# A-1_SINGLE_STEP_2021-06-04.net
KiCad netlist of a schematic drawn in EasyEDA
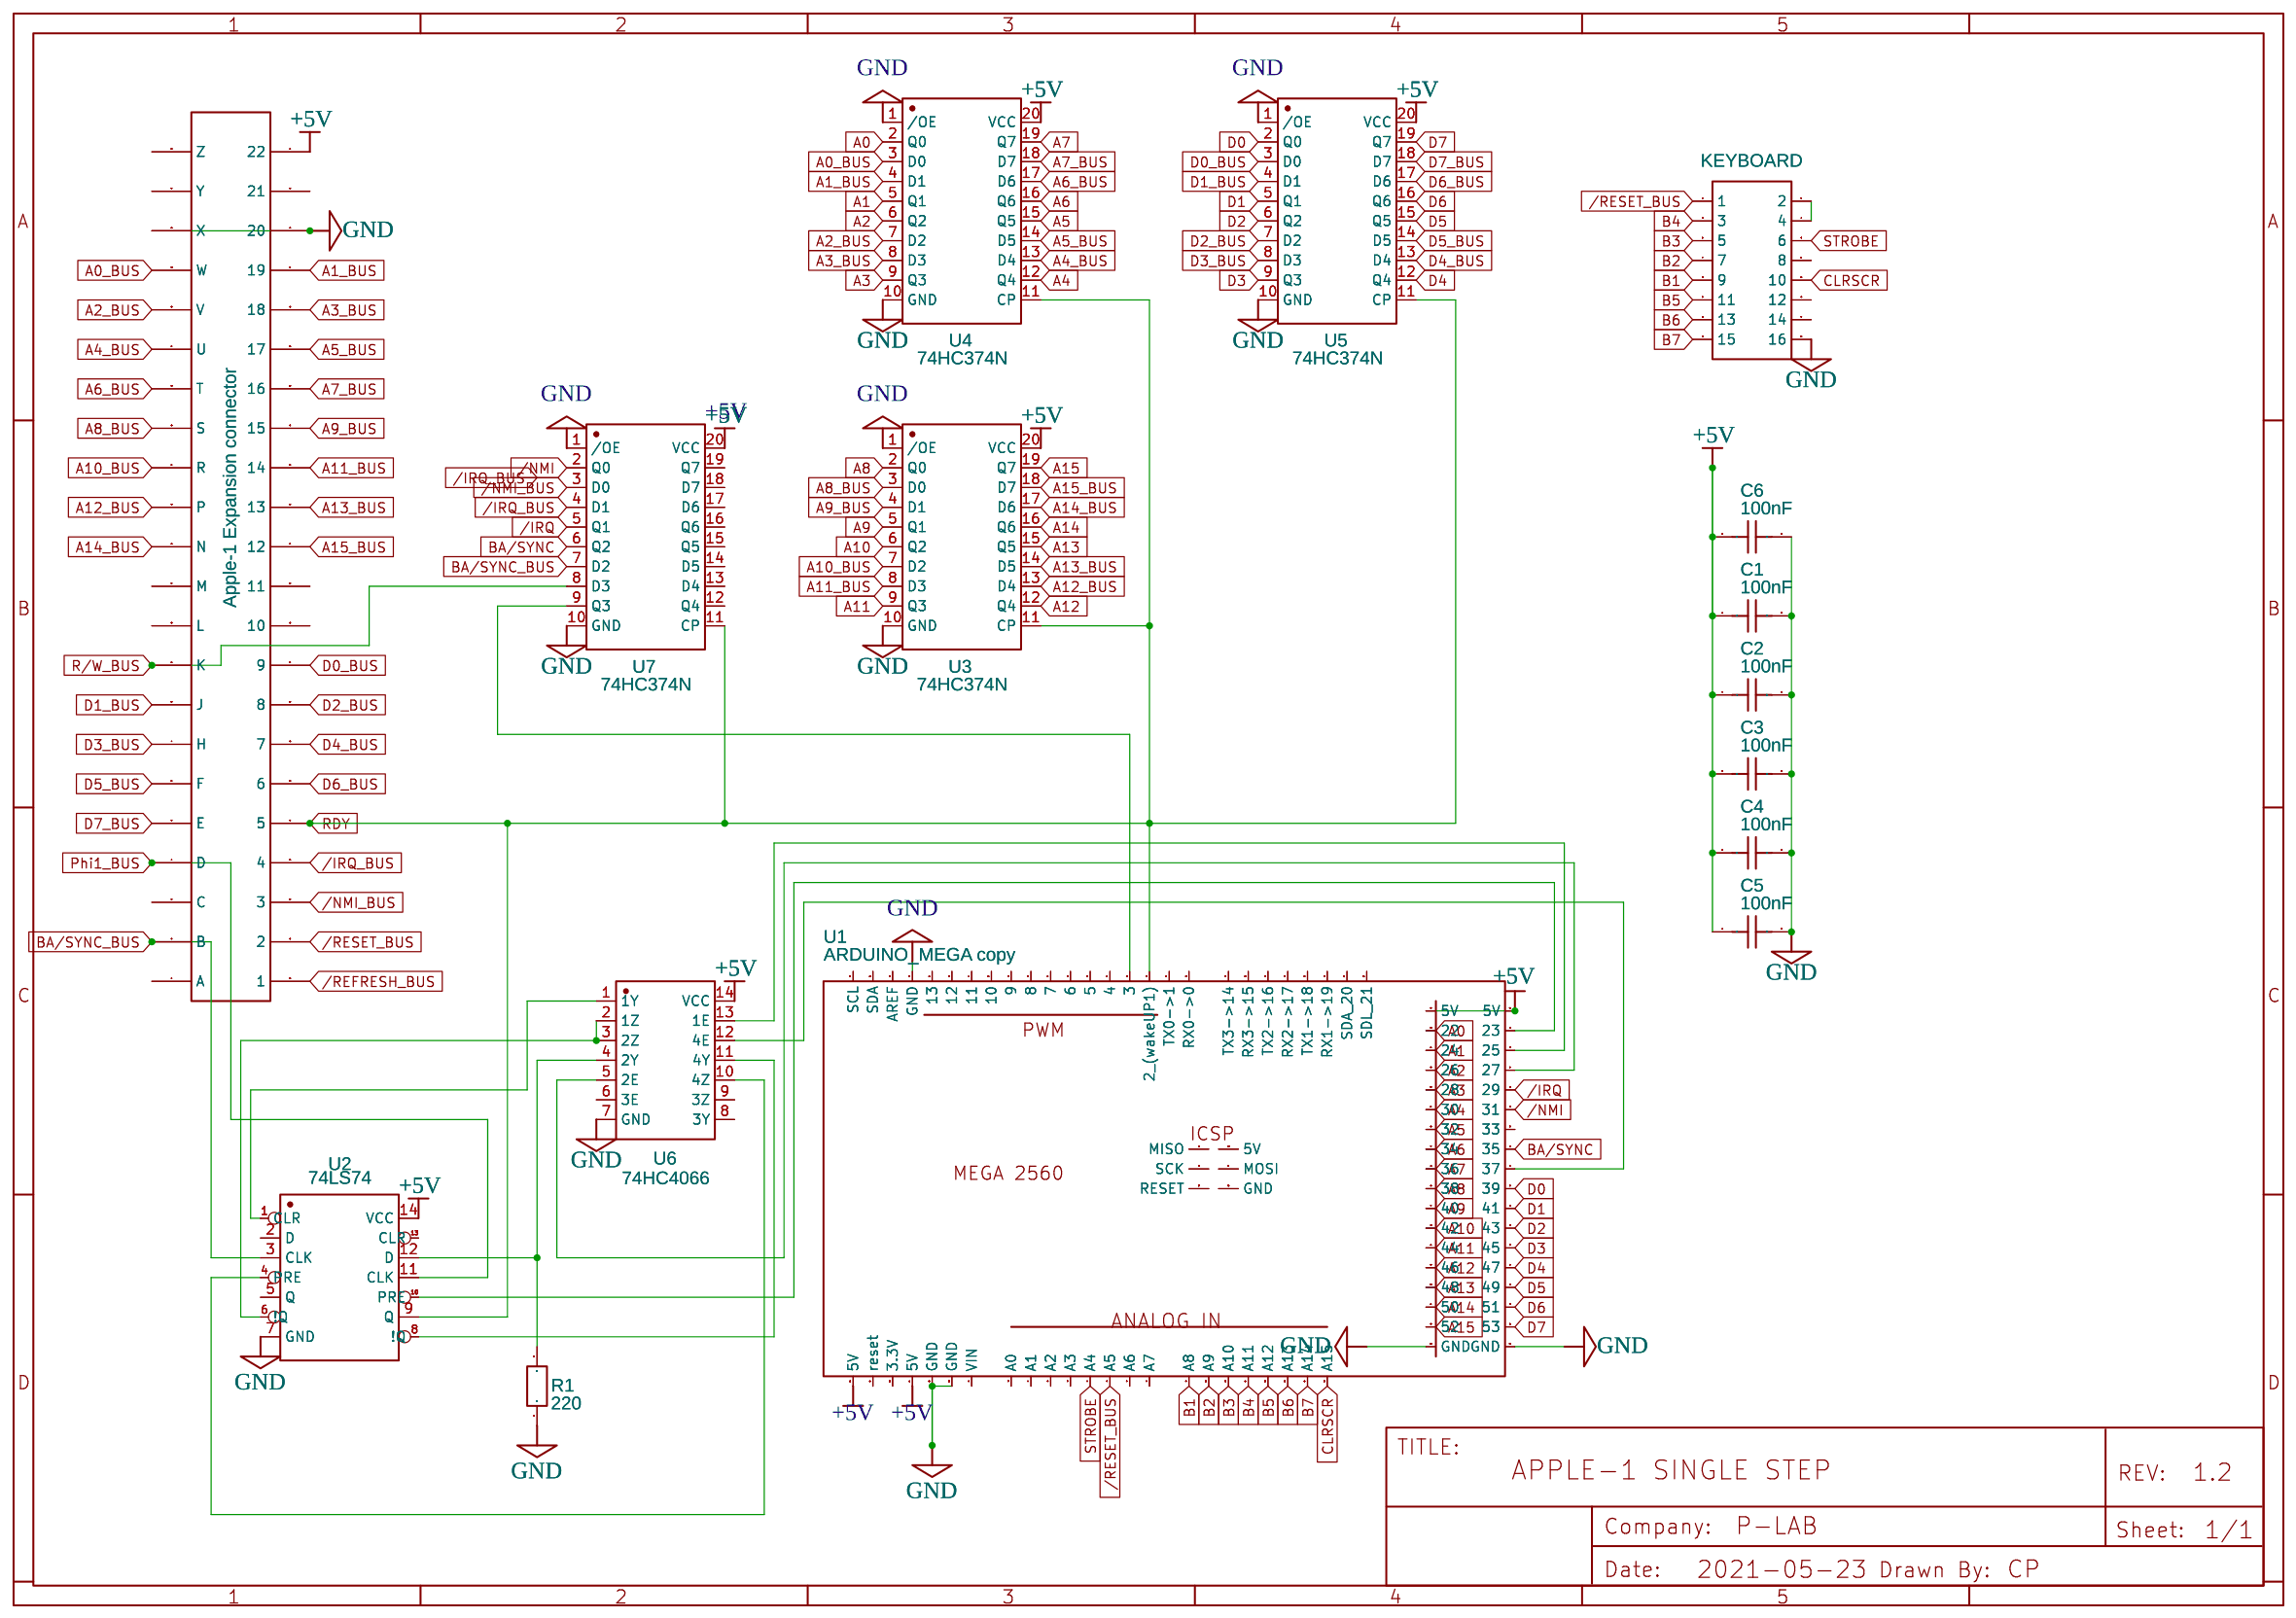
[diagram p0: schematic sheet]

(export (version "E")
  (design (tool "Eeschema 10.0.6"))
  (components
    (comp (ref "C1")
      (value "100nF")
      (fields
        (field (name "BOM_Manufacturer Part") "CT4G-0805-2X1-50V-0.1uF-K")
        (field (name "BOM_Supplier Part") "C141981")
      )
      (libsource (lib "") (part "CT4G-0805-2X1-50V-0.1UF-K"))
    )
    (comp (ref "C2")
      (value "100nF")
      (fields
        (field (name "BOM_Manufacturer Part") "CT4G-0805-2X1-50V-0.1uF-K")
        (field (name "BOM_Supplier Part") "C141981")
      )
      (libsource (lib "") (part "CT4G-0805-2X1-50V-0.1UF-K"))
    )
    (comp (ref "C3")
      (value "100nF")
      (fields
        (field (name "BOM_Manufacturer Part") "CT4G-0805-2X1-50V-0.1uF-K")
        (field (name "BOM_Supplier Part") "C141981")
      )
      (libsource (lib "") (part "CT4G-0805-2X1-50V-0.1UF-K"))
    )
    (comp (ref "C4")
      (value "100nF")
      (fields
        (field (name "BOM_Manufacturer Part") "CT4G-0805-2X1-50V-0.1uF-K")
        (field (name "BOM_Supplier Part") "C141981")
      )
      (libsource (lib "") (part "CT4G-0805-2X1-50V-0.1UF-K"))
    )
    (comp (ref "C5")
      (value "100nF")
      (fields
        (field (name "BOM_Manufacturer Part") "CT4G-0805-2X1-50V-0.1uF-K")
        (field (name "BOM_Supplier Part") "C141981")
      )
      (libsource (lib "") (part "CT4G-0805-2X1-50V-0.1UF-K"))
    )
    (comp (ref "C6")
      (value "100nF")
      (fields
        (field (name "BOM_Manufacturer Part") "CT4G-0805-2X1-50V-0.1uF-K")
        (field (name "BOM_Supplier Part") "C141981")
      )
      (libsource (lib "") (part "CT4G-0805-2X1-50V-0.1UF-K"))
    )
    (comp (ref "J1")
      (value "Apple-1 Expansion connector")
      (fields (field (name "BOM_Manufacturer Part") "306-018-520-102"))
      (libsource (lib "") (part "EDAC_Card_Edge_Female_2x22_pin_3.96mm"))
    )
    (comp (ref "KEYBOARD") (value "Header 2x8") (libsource (lib "") (part "Header 2x8")))
    (comp (ref "R1")
      (value "220")
      (fields
        (field (name "BOM_Manufacturer Part") "RN 1/4W 2R F T/B A1")
        (field (name "BOM_Supplier Part") "C410658")
      )
      (libsource (lib "") (part "RN 1/4W 2R F T/B A1"))
    )
    (comp (ref "U1")
      (value "ARDUINO_MEGA copy")
      (fields (field (name "BOM_Manufacturer Part") "ARDUINO MEGA"))
      (libsource (lib "") (part "ARDUINO_MEGA copy"))
    )
    (comp (ref "U2") (value "74LS74") (libsource (lib "") (part "7474")))
    (comp (ref "U3") (value "74HC374N") (libsource (lib "") (part "74HC374N")))
    (comp (ref "U4") (value "74HC374N") (libsource (lib "") (part "74HC374N")))
    (comp (ref "U5") (value "74HC374N") (libsource (lib "") (part "74HC374N")))
    (comp (ref "U6")
      (value "74HC4066")
      (fields
        (field (name "BOM_Manufacturer Part") "74HC4066D-Q100,118")
        (field (name "BOM_Supplier Part") "C547030")
      )
      (libsource (lib "") (part "74HC4066D-Q100,118"))
    )
    (comp (ref "U7") (value "74HC374N") (libsource (lib "") (part "74HC374N")))
  )
  (nets
    (net (code "1") (name "+5V") (class "Default")
      (node (ref "C1") (pin "1") (pinfunction "1_1") (pintype "unspecified"))
      (node (ref "C2") (pin "1") (pinfunction "1_1") (pintype "unspecified"))
      (node (ref "C3") (pin "1") (pinfunction "1_1") (pintype "unspecified"))
      (node (ref "C4") (pin "1") (pinfunction "1_1") (pintype "unspecified"))
      (node (ref "C5") (pin "1") (pinfunction "1_1") (pintype "unspecified"))
      (node (ref "C6") (pin "1") (pinfunction "1_1") (pintype "unspecified"))
      (node (ref "J1") (pin "44") (pinfunction "22_44") (pintype "unspecified"))
      (node (ref "U1") (pin "5V") (pinfunction "5V_5V") (pintype "unspecified"))
      (node (ref "U1") (pin "5V.") (pinfunction "5V_5V.") (pintype "unspecified"))
      (node (ref "U1") (pin "5V..") (pinfunction "5V_5V..") (pintype "unspecified"))
      (node (ref "U1") (pin "5V...") (pinfunction "5V_5V...") (pintype "unspecified"))
      (node (ref "U2") (pin "14") (pinfunction "VCC_14") (pintype "unspecified"))
      (node (ref "U3") (pin "20") (pinfunction "VCC_20") (pintype "unspecified"))
      (node (ref "U4") (pin "20") (pinfunction "VCC_20") (pintype "unspecified"))
      (node (ref "U5") (pin "20") (pinfunction "VCC_20") (pintype "unspecified"))
      (node (ref "U6") (pin "14") (pinfunction "VCC_14") (pintype "unspecified"))
      (node (ref "U7") (pin "20") (pinfunction "VCC_20") (pintype "unspecified"))
    )
    (net (code "2") (name "A0") (class "Default")
      (node (ref "U1") (pin "29") (pinfunction "22_29") (pintype "unspecified"))
      (node (ref "U4") (pin "2") (pinfunction "Q0_2") (pintype "unspecified"))
    )
    (net (code "3") (name "A0_BUS") (class "Default")
      (node (ref "J1") (pin "19") (pinfunction "W_19") (pintype "unspecified"))
      (node (ref "U4") (pin "3") (pinfunction "D0_3") (pintype "unspecified"))
    )
    (net (code "4") (name "A1") (class "Default")
      (node (ref "U1") (pin "31") (pinfunction "24_31") (pintype "unspecified"))
      (node (ref "U4") (pin "5") (pinfunction "Q1_5") (pintype "unspecified"))
    )
    (net (code "5") (name "A1_BUS") (class "Default")
      (node (ref "J1") (pin "41") (pinfunction "19_41") (pintype "unspecified"))
      (node (ref "U4") (pin "4") (pinfunction "D1_4") (pintype "unspecified"))
    )
    (net (code "6") (name "A2") (class "Default")
      (node (ref "U1") (pin "33") (pinfunction "26_33") (pintype "unspecified"))
      (node (ref "U4") (pin "6") (pinfunction "Q2_6") (pintype "unspecified"))
    )
    (net (code "7") (name "A2_BUS") (class "Default")
      (node (ref "J1") (pin "18") (pinfunction "V_18") (pintype "unspecified"))
      (node (ref "U4") (pin "7") (pinfunction "D2_7") (pintype "unspecified"))
    )
    (net (code "8") (name "A3") (class "Default")
      (node (ref "U1") (pin "35") (pinfunction "28_35") (pintype "unspecified"))
      (node (ref "U4") (pin "9") (pinfunction "Q3_9") (pintype "unspecified"))
    )
    (net (code "9") (name "A3_BUS") (class "Default")
      (node (ref "J1") (pin "40") (pinfunction "18_40") (pintype "unspecified"))
      (node (ref "U4") (pin "8") (pinfunction "D3_8") (pintype "unspecified"))
    )
    (net (code "10") (name "A4") (class "Default")
      (node (ref "U1") (pin "37") (pinfunction "30_37") (pintype "unspecified"))
      (node (ref "U4") (pin "12") (pinfunction "Q4_12") (pintype "unspecified"))
    )
    (net (code "11") (name "A4_BUS") (class "Default")
      (node (ref "J1") (pin "17") (pinfunction "U_17") (pintype "unspecified"))
      (node (ref "U4") (pin "13") (pinfunction "D4_13") (pintype "unspecified"))
    )
    (net (code "12") (name "A5") (class "Default")
      (node (ref "U1") (pin "39") (pinfunction "32_39") (pintype "unspecified"))
      (node (ref "U4") (pin "15") (pinfunction "Q5_15") (pintype "unspecified"))
    )
    (net (code "13") (name "A5_BUS") (class "Default")
      (node (ref "J1") (pin "39") (pinfunction "17_39") (pintype "unspecified"))
      (node (ref "U4") (pin "14") (pinfunction "D5_14") (pintype "unspecified"))
    )
    (net (code "14") (name "A6") (class "Default")
      (node (ref "U1") (pin "41") (pinfunction "34_41") (pintype "unspecified"))
      (node (ref "U4") (pin "16") (pinfunction "Q6_16") (pintype "unspecified"))
    )
    (net (code "15") (name "A6_BUS") (class "Default")
      (node (ref "J1") (pin "16") (pinfunction "T_16") (pintype "unspecified"))
      (node (ref "U4") (pin "17") (pinfunction "D6_17") (pintype "unspecified"))
    )
    (net (code "16") (name "A7") (class "Default")
      (node (ref "U1") (pin "43") (pinfunction "36_43") (pintype "unspecified"))
      (node (ref "U4") (pin "19") (pinfunction "Q7_19") (pintype "unspecified"))
    )
    (net (code "17") (name "A7_BUS") (class "Default")
      (node (ref "J1") (pin "38") (pinfunction "16_38") (pintype "unspecified"))
      (node (ref "U4") (pin "18") (pinfunction "D7_18") (pintype "unspecified"))
    )
    (net (code "18") (name "A8") (class "Default")
      (node (ref "U1") (pin "45") (pinfunction "38_45") (pintype "unspecified"))
      (node (ref "U3") (pin "2") (pinfunction "Q0_2") (pintype "unspecified"))
    )
    (net (code "19") (name "A8_BUS") (class "Default")
      (node (ref "J1") (pin "15") (pinfunction "S_15") (pintype "unspecified"))
      (node (ref "U3") (pin "3") (pinfunction "D0_3") (pintype "unspecified"))
    )
    (net (code "20") (name "A9") (class "Default")
      (node (ref "U1") (pin "47") (pinfunction "40_47") (pintype "unspecified"))
      (node (ref "U3") (pin "5") (pinfunction "Q1_5") (pintype "unspecified"))
    )
    (net (code "21") (name "A9_BUS") (class "Default")
      (node (ref "J1") (pin "37") (pinfunction "15_37") (pintype "unspecified"))
      (node (ref "U3") (pin "4") (pinfunction "D1_4") (pintype "unspecified"))
    )
    (net (code "22") (name "A10") (class "Default")
      (node (ref "U1") (pin "49") (pinfunction "42_49") (pintype "unspecified"))
      (node (ref "U3") (pin "6") (pinfunction "Q2_6") (pintype "unspecified"))
    )
    (net (code "23") (name "A10_BUS") (class "Default")
      (node (ref "J1") (pin "14") (pinfunction "R_14") (pintype "unspecified"))
      (node (ref "U3") (pin "7") (pinfunction "D2_7") (pintype "unspecified"))
    )
    (net (code "24") (name "A11") (class "Default")
      (node (ref "U1") (pin "51") (pinfunction "44_51") (pintype "unspecified"))
      (node (ref "U3") (pin "9") (pinfunction "Q3_9") (pintype "unspecified"))
    )
    (net (code "25") (name "A11_BUS") (class "Default")
      (node (ref "J1") (pin "36") (pinfunction "14_36") (pintype "unspecified"))
      (node (ref "U3") (pin "8") (pinfunction "D3_8") (pintype "unspecified"))
    )
    (net (code "26") (name "A12") (class "Default")
      (node (ref "U1") (pin "53") (pinfunction "46_53") (pintype "unspecified"))
      (node (ref "U3") (pin "12") (pinfunction "Q4_12") (pintype "unspecified"))
    )
    (net (code "27") (name "A12_BUS") (class "Default")
      (node (ref "J1") (pin "13") (pinfunction "P_13") (pintype "unspecified"))
      (node (ref "U3") (pin "13") (pinfunction "D4_13") (pintype "unspecified"))
    )
    (net (code "28") (name "A13") (class "Default")
      (node (ref "U1") (pin "55") (pinfunction "48_55") (pintype "unspecified"))
      (node (ref "U3") (pin "15") (pinfunction "Q5_15") (pintype "unspecified"))
    )
    (net (code "29") (name "A13_BUS") (class "Default")
      (node (ref "J1") (pin "35") (pinfunction "13_35") (pintype "unspecified"))
      (node (ref "U3") (pin "14") (pinfunction "D5_14") (pintype "unspecified"))
    )
    (net (code "30") (name "A14") (class "Default")
      (node (ref "U1") (pin "57") (pinfunction "50_57") (pintype "unspecified"))
      (node (ref "U3") (pin "16") (pinfunction "Q6_16") (pintype "unspecified"))
    )
    (net (code "31") (name "A14_BUS") (class "Default")
      (node (ref "J1") (pin "12") (pinfunction "N_12") (pintype "unspecified"))
      (node (ref "U3") (pin "17") (pinfunction "D6_17") (pintype "unspecified"))
    )
    (net (code "32") (name "A15") (class "Default")
      (node (ref "U1") (pin "59") (pinfunction "52_59") (pintype "unspecified"))
      (node (ref "U3") (pin "19") (pinfunction "Q7_19") (pintype "unspecified"))
    )
    (net (code "33") (name "A15_BUS") (class "Default")
      (node (ref "J1") (pin "34") (pinfunction "12_34") (pintype "unspecified"))
      (node (ref "U3") (pin "18") (pinfunction "D7_18") (pintype "unspecified"))
    )
    (net (code "34") (name "B1") (class "Default")
      (node (ref "KEYBOARD") (pin "9") (pinfunction "9_9") (pintype "input"))
      (node (ref "U1") (pin "70") (pinfunction "A8_70") (pintype "unspecified"))
    )
    (net (code "35") (name "B2") (class "Default")
      (node (ref "KEYBOARD") (pin "7") (pinfunction "7_7") (pintype "input"))
      (node (ref "U1") (pin "69") (pinfunction "A9_69") (pintype "unspecified"))
    )
    (net (code "36") (name "B3") (class "Default")
      (node (ref "KEYBOARD") (pin "5") (pinfunction "5_5") (pintype "input"))
      (node (ref "U1") (pin "68") (pinfunction "A10_68") (pintype "unspecified"))
    )
    (net (code "37") (name "B4") (class "Default")
      (node (ref "KEYBOARD") (pin "3") (pinfunction "3_3") (pintype "input"))
      (node (ref "U1") (pin "67") (pinfunction "A11_67") (pintype "unspecified"))
    )
    (net (code "38") (name "B5") (class "Default")
      (node (ref "KEYBOARD") (pin "11") (pinfunction "11_11") (pintype "input"))
      (node (ref "U1") (pin "66") (pinfunction "A12_66") (pintype "unspecified"))
    )
    (net (code "39") (name "B6") (class "Default")
      (node (ref "KEYBOARD") (pin "13") (pinfunction "13_13") (pintype "input"))
      (node (ref "U1") (pin "65") (pinfunction "A13_65") (pintype "unspecified"))
    )
    (net (code "40") (name "B7") (class "Default")
      (node (ref "KEYBOARD") (pin "15") (pinfunction "15_15") (pintype "input"))
      (node (ref "U1") (pin "64") (pinfunction "A14_64") (pintype "unspecified"))
    )
    (net (code "41") (name "BA{slash}SYNC") (class "Default")
      (node (ref "U1") (pin "42") (pinfunction "35_42") (pintype "unspecified"))
      (node (ref "U7") (pin "6") (pinfunction "Q2_6") (pintype "unspecified"))
    )
    (net (code "42") (name "BA{slash}SYNC_BUS") (class "Default")
      (node (ref "J1") (pin "2") (pinfunction "B_2") (pintype "unspecified"))
      (node (ref "U2") (pin "3") (pinfunction "CLK_3") (pintype "unspecified"))
      (node (ref "U7") (pin "7") (pinfunction "D2_7") (pintype "unspecified"))
    )
    (net (code "43") (name "CLRSCR") (class "Default")
      (node (ref "KEYBOARD") (pin "10") (pinfunction "10_10") (pintype "input"))
      (node (ref "U1") (pin "63") (pinfunction "A15_63") (pintype "unspecified"))
    )
    (net (code "44") (name "D0") (class "Default")
      (node (ref "U1") (pin "46") (pinfunction "39_46") (pintype "unspecified"))
      (node (ref "U5") (pin "2") (pinfunction "Q0_2") (pintype "unspecified"))
    )
    (net (code "45") (name "D0_BUS") (class "Default")
      (node (ref "J1") (pin "31") (pinfunction "9_31") (pintype "unspecified"))
      (node (ref "U5") (pin "3") (pinfunction "D0_3") (pintype "unspecified"))
    )
    (net (code "46") (name "D1") (class "Default")
      (node (ref "U1") (pin "48") (pinfunction "41_48") (pintype "unspecified"))
      (node (ref "U5") (pin "5") (pinfunction "Q1_5") (pintype "unspecified"))
    )
    (net (code "47") (name "D1_BUS") (class "Default")
      (node (ref "J1") (pin "8") (pinfunction "J_8") (pintype "unspecified"))
      (node (ref "U5") (pin "4") (pinfunction "D1_4") (pintype "unspecified"))
    )
    (net (code "48") (name "D2") (class "Default")
      (node (ref "U1") (pin "50") (pinfunction "43_50") (pintype "unspecified"))
      (node (ref "U5") (pin "6") (pinfunction "Q2_6") (pintype "unspecified"))
    )
    (net (code "49") (name "D2_BUS") (class "Default")
      (node (ref "J1") (pin "30") (pinfunction "8_30") (pintype "unspecified"))
      (node (ref "U5") (pin "7") (pinfunction "D2_7") (pintype "unspecified"))
    )
    (net (code "50") (name "D3") (class "Default")
      (node (ref "U1") (pin "52") (pinfunction "45_52") (pintype "unspecified"))
      (node (ref "U5") (pin "9") (pinfunction "Q3_9") (pintype "unspecified"))
    )
    (net (code "51") (name "D3_BUS") (class "Default")
      (node (ref "J1") (pin "7") (pinfunction "H_7") (pintype "unspecified"))
      (node (ref "U5") (pin "8") (pinfunction "D3_8") (pintype "unspecified"))
    )
    (net (code "52") (name "D4") (class "Default")
      (node (ref "U1") (pin "54") (pinfunction "47_54") (pintype "unspecified"))
      (node (ref "U5") (pin "12") (pinfunction "Q4_12") (pintype "unspecified"))
    )
    (net (code "53") (name "D4_BUS") (class "Default")
      (node (ref "J1") (pin "29") (pinfunction "7_29") (pintype "unspecified"))
      (node (ref "U5") (pin "13") (pinfunction "D4_13") (pintype "unspecified"))
    )
    (net (code "54") (name "D5") (class "Default")
      (node (ref "U1") (pin "56") (pinfunction "49_56") (pintype "unspecified"))
      (node (ref "U5") (pin "15") (pinfunction "Q5_15") (pintype "unspecified"))
    )
    (net (code "55") (name "D5_BUS") (class "Default")
      (node (ref "J1") (pin "6") (pinfunction "F_6") (pintype "unspecified"))
      (node (ref "U5") (pin "14") (pinfunction "D5_14") (pintype "unspecified"))
    )
    (net (code "56") (name "D6") (class "Default")
      (node (ref "U1") (pin "58") (pinfunction "51_58") (pintype "unspecified"))
      (node (ref "U5") (pin "16") (pinfunction "Q6_16") (pintype "unspecified"))
    )
    (net (code "57") (name "D6_BUS") (class "Default")
      (node (ref "J1") (pin "28") (pinfunction "6_28") (pintype "unspecified"))
      (node (ref "U5") (pin "17") (pinfunction "D6_17") (pintype "unspecified"))
    )
    (net (code "58") (name "D7") (class "Default")
      (node (ref "U1") (pin "60") (pinfunction "53_60") (pintype "unspecified"))
      (node (ref "U5") (pin "19") (pinfunction "Q7_19") (pintype "unspecified"))
    )
    (net (code "59") (name "D7_BUS") (class "Default")
      (node (ref "J1") (pin "5") (pinfunction "E_5") (pintype "unspecified"))
      (node (ref "U5") (pin "18") (pinfunction "D7_18") (pintype "unspecified"))
    )
    (net (code "60") (name "GND") (class "Default")
      (node (ref "C1") (pin "2") (pinfunction "2_2") (pintype "unspecified"))
      (node (ref "C2") (pin "2") (pinfunction "2_2") (pintype "unspecified"))
      (node (ref "C3") (pin "2") (pinfunction "2_2") (pintype "unspecified"))
      (node (ref "C4") (pin "2") (pinfunction "2_2") (pintype "unspecified"))
      (node (ref "C5") (pin "2") (pinfunction "2_2") (pintype "unspecified"))
      (node (ref "C6") (pin "2") (pinfunction "2_2") (pintype "unspecified"))
      (node (ref "J1") (pin "20") (pinfunction "X_20") (pintype "unspecified"))
      (node (ref "J1") (pin "42") (pinfunction "20_42") (pintype "unspecified"))
      (node (ref "KEYBOARD") (pin "16") (pinfunction "16_16") (pintype "input"))
      (node (ref "R1") (pin "1") (pinfunction "1_1") (pintype "unspecified"))
      (node (ref "U1") (pin "GND") (pinfunction "GND_GND") (pintype "unspecified"))
      (node (ref "U2") (pin "7") (pinfunction "GND_7") (pintype "unspecified"))
      (node (ref "U3") (pin "1") (pinfunction "/OE_1") (pintype "unspecified"))
      (node (ref "U3") (pin "10") (pinfunction "GND_10") (pintype "unspecified"))
      (node (ref "U4") (pin "1") (pinfunction "/OE_1") (pintype "unspecified"))
      (node (ref "U4") (pin "10") (pinfunction "GND_10") (pintype "unspecified"))
      (node (ref "U5") (pin "1") (pinfunction "/OE_1") (pintype "unspecified"))
      (node (ref "U5") (pin "10") (pinfunction "GND_10") (pintype "unspecified"))
      (node (ref "U6") (pin "7") (pinfunction "GND_7") (pintype "unspecified"))
      (node (ref "U7") (pin "1") (pinfunction "/OE_1") (pintype "unspecified"))
      (node (ref "U7") (pin "10") (pinfunction "GND_10") (pintype "unspecified"))
    )
    (net (code "61") (name "Net-(KEYBOARD-Pad2)") (class "Default")
      (node (ref "KEYBOARD") (pin "2") (pinfunction "2_2") (pintype "input"))
      (node (ref "KEYBOARD") (pin "4") (pinfunction "4_4") (pintype "input"))
    )
    (net (code "62") (name "Net-(U1-3)") (class "Default")
      (node (ref "U1") (pin "15") (pinfunction "3_15") (pintype "unspecified"))
      (node (ref "U7") (pin "9") (pinfunction "Q3_9") (pintype "unspecified"))
    )
    (net (code "63") (name "Net-(U1-23)") (class "Default")
      (node (ref "U1") (pin "30") (pinfunction "23_30") (pintype "unspecified"))
      (node (ref "U2") (pin "10") (pinfunction "PRE_10") (pintype "unspecified"))
    )
    (net (code "64") (name "Net-(U1-25)") (class "Default")
      (node (ref "U1") (pin "32") (pinfunction "25_32") (pintype "unspecified"))
      (node (ref "U6") (pin "13") (pinfunction "1E_13") (pintype "unspecified"))
    )
    (net (code "65") (name "Net-(U1-27)") (class "Default")
      (node (ref "U1") (pin "34") (pinfunction "27_34") (pintype "unspecified"))
      (node (ref "U6") (pin "5") (pinfunction "2E_5") (pintype "unspecified"))
    )
    (net (code "66") (name "Net-(U1-37)") (class "Default")
      (node (ref "U1") (pin "44") (pinfunction "37_44") (pintype "unspecified"))
      (node (ref "U6") (pin "12") (pinfunction "4E_12") (pintype "unspecified"))
    )
    (net (code "67") (name "Net-(U6-1Y)") (class "Default")
      (node (ref "U2") (pin "1") (pinfunction "CLR_1") (pintype "unspecified"))
      (node (ref "U6") (pin "1") (pinfunction "1Y_1") (pintype "unspecified"))
    )
    (net (code "68") (name "Net-(U6-1Z)") (class "Default")
      (node (ref "U2") (pin "6") (pinfunction "!Q_6") (pintype "unspecified"))
      (node (ref "U6") (pin "2") (pinfunction "1Z_2") (pintype "unspecified"))
      (node (ref "U6") (pin "3") (pinfunction "2Z_3") (pintype "unspecified"))
    )
    (net (code "69") (name "Net-(U6-2Y)") (class "Default")
      (node (ref "R1") (pin "2") (pinfunction "2_2") (pintype "unspecified"))
      (node (ref "U2") (pin "12") (pinfunction "D_12") (pintype "unspecified"))
      (node (ref "U6") (pin "4") (pinfunction "2Y_4") (pintype "unspecified"))
    )
    (net (code "70") (name "Net-(U6-4Y)") (class "Default")
      (node (ref "U2") (pin "8") (pinfunction "!Q_8") (pintype "unspecified"))
      (node (ref "U6") (pin "11") (pinfunction "4Y_11") (pintype "unspecified"))
    )
    (net (code "71") (name "Net-(U6-4Z)") (class "Default")
      (node (ref "U2") (pin "4") (pinfunction "PRE_4") (pintype "unspecified"))
      (node (ref "U6") (pin "10") (pinfunction "4Z_10") (pintype "unspecified"))
    )
    (net (code "72") (name "Phi1_BUS") (class "Default")
      (node (ref "J1") (pin "4") (pinfunction "D_4") (pintype "unspecified"))
      (node (ref "U2") (pin "11") (pinfunction "CLK_11") (pintype "unspecified"))
    )
    (net (code "73") (name "RDY") (class "Default")
      (node (ref "J1") (pin "27") (pinfunction "5_27") (pintype "unspecified"))
      (node (ref "U1") (pin "16") (pinfunction "2_(wakeUP1)_16") (pintype "unspecified"))
      (node (ref "U2") (pin "9") (pinfunction "Q_9") (pintype "unspecified"))
      (node (ref "U3") (pin "11") (pinfunction "CP_11") (pintype "unspecified"))
      (node (ref "U4") (pin "11") (pinfunction "CP_11") (pintype "unspecified"))
      (node (ref "U5") (pin "11") (pinfunction "CP_11") (pintype "unspecified"))
      (node (ref "U7") (pin "11") (pinfunction "CP_11") (pintype "unspecified"))
    )
    (net (code "74") (name "R{slash}W_BUS") (class "Default")
      (node (ref "J1") (pin "9") (pinfunction "K_9") (pintype "unspecified"))
      (node (ref "U7") (pin "8") (pinfunction "D3_8") (pintype "unspecified"))
    )
    (net (code "75") (name "STROBE") (class "Default")
      (node (ref "KEYBOARD") (pin "6") (pinfunction "6_6") (pintype "input"))
      (node (ref "U1") (pin "74") (pinfunction "A4_74") (pintype "unspecified"))
    )
    (net (code "76") (name "unconnected-(J1-10-Pad32)") (class "Default")
      (node (ref "J1") (pin "32") (pinfunction "10_32") (pintype "unspecified"))
    )
    (net (code "77") (name "unconnected-(J1-11-Pad33)") (class "Default")
      (node (ref "J1") (pin "33") (pinfunction "11_33") (pintype "unspecified"))
    )
    (net (code "78") (name "unconnected-(J1-21-Pad43)") (class "Default")
      (node (ref "J1") (pin "43") (pinfunction "21_43") (pintype "unspecified"))
    )
    (net (code "79") (name "unconnected-(J1-A-Pad1)") (class "Default")
      (node (ref "J1") (pin "1") (pinfunction "A_1") (pintype "unspecified"))
    )
    (net (code "80") (name "unconnected-(J1-C-Pad3)") (class "Default")
      (node (ref "J1") (pin "3") (pinfunction "C_3") (pintype "unspecified"))
    )
    (net (code "81") (name "unconnected-(J1-L-Pad10)") (class "Default")
      (node (ref "J1") (pin "10") (pinfunction "L_10") (pintype "unspecified"))
    )
    (net (code "82") (name "unconnected-(J1-M-Pad11)") (class "Default")
      (node (ref "J1") (pin "11") (pinfunction "M_11") (pintype "unspecified"))
    )
    (net (code "83") (name "unconnected-(J1-Y-Pad21)") (class "Default")
      (node (ref "J1") (pin "21") (pinfunction "Y_21") (pintype "unspecified"))
    )
    (net (code "84") (name "unconnected-(J1-Z-Pad22)") (class "Default")
      (node (ref "J1") (pin "22") (pinfunction "Z_22") (pintype "unspecified"))
    )
    (net (code "85") (name "unconnected-(KEYBOARD-Pad8)") (class "Default")
      (node (ref "KEYBOARD") (pin "8") (pinfunction "8_8") (pintype "input"))
    )
    (net (code "86") (name "unconnected-(KEYBOARD-Pad12)") (class "Default")
      (node (ref "KEYBOARD") (pin "12") (pinfunction "12_12") (pintype "input"))
    )
    (net (code "87") (name "unconnected-(KEYBOARD-Pad14)") (class "Default")
      (node (ref "KEYBOARD") (pin "14") (pinfunction "14_14") (pintype "input"))
    )
    (net (code "88") (name "unconnected-(U1-3.3V-Pad83)") (class "Default")
      (node (ref "U1") (pin "83") (pinfunction "3.3V_83") (pintype "unspecified"))
    )
    (net (code "89") (name "unconnected-(U1-4-Pad14)") (class "Default")
      (node (ref "U1") (pin "14") (pinfunction "4_14") (pintype "unspecified"))
    )
    (net (code "90") (name "unconnected-(U1-5-Pad13)") (class "Default")
      (node (ref "U1") (pin "13") (pinfunction "5_13") (pintype "unspecified"))
    )
    (net (code "91") (name "unconnected-(U1-5V-Pad5VICSP)") (class "Default")
      (node (ref "U1") (pin "5VICSP") (pinfunction "5V_5VICSP") (pintype "unspecified"))
    )
    (net (code "92") (name "unconnected-(U1-6-Pad12)") (class "Default")
      (node (ref "U1") (pin "12") (pinfunction "6_12") (pintype "unspecified"))
    )
    (net (code "93") (name "unconnected-(U1-7-Pad11)") (class "Default")
      (node (ref "U1") (pin "11") (pinfunction "7_11") (pintype "unspecified"))
    )
    (net (code "94") (name "unconnected-(U1-8-Pad10)") (class "Default")
      (node (ref "U1") (pin "10") (pinfunction "8_10") (pintype "unspecified"))
    )
    (net (code "95") (name "unconnected-(U1-10-Pad8)") (class "Default")
      (node (ref "U1") (pin "8") (pinfunction "10_8") (pintype "unspecified"))
    )
    (net (code "96") (name "unconnected-(U1-11-Pad7)") (class "Default")
      (node (ref "U1") (pin "7") (pinfunction "11_7") (pintype "unspecified"))
    )
    (net (code "97") (name "unconnected-(U1-12-Pad6)") (class "Default")
      (node (ref "U1") (pin "6") (pinfunction "12_6") (pintype "unspecified"))
    )
    (net (code "98") (name "unconnected-(U1-13-Pad5)") (class "Default")
      (node (ref "U1") (pin "5") (pinfunction "13_5") (pintype "unspecified"))
    )
    (net (code "99") (name "unconnected-(U1-33-Pad40)") (class "Default")
      (node (ref "U1") (pin "40") (pinfunction "33_40") (pintype "unspecified"))
    )
    (net (code "100") (name "unconnected-(U1-A0-Pad78)") (class "Default")
      (node (ref "U1") (pin "78") (pinfunction "A0_78") (pintype "unspecified"))
    )
    (net (code "101") (name "unconnected-(U1-A1-Pad77)") (class "Default")
      (node (ref "U1") (pin "77") (pinfunction "A1_77") (pintype "unspecified"))
    )
    (net (code "102") (name "unconnected-(U1-A2-Pad76)") (class "Default")
      (node (ref "U1") (pin "76") (pinfunction "A2_76") (pintype "unspecified"))
    )
    (net (code "103") (name "unconnected-(U1-A3-Pad75)") (class "Default")
      (node (ref "U1") (pin "75") (pinfunction "A3_75") (pintype "unspecified"))
    )
    (net (code "104") (name "unconnected-(U1-A6-Pad72)") (class "Default")
      (node (ref "U1") (pin "72") (pinfunction "A6_72") (pintype "unspecified"))
    )
    (net (code "105") (name "unconnected-(U1-A7-Pad71)") (class "Default")
      (node (ref "U1") (pin "71") (pinfunction "A7_71") (pintype "unspecified"))
    )
    (net (code "106") (name "unconnected-(U1-AREF-Pad3)") (class "Default")
      (node (ref "U1") (pin "3") (pinfunction "AREF_3") (pintype "unspecified"))
    )
    (net (code "107") (name "unconnected-(U1-MISO-Pad86)") (class "Default")
      (node (ref "U1") (pin "86") (pinfunction "MISO_86") (pintype "unspecified"))
    )
    (net (code "108") (name "unconnected-(U1-MOSI-Pad90)") (class "Default")
      (node (ref "U1") (pin "90") (pinfunction "MOSI_90") (pintype "unspecified"))
    )
    (net (code "109") (name "unconnected-(U1-Pad9)") (class "Default")
      (node (ref "U1") (pin "9") (pinfunction "9_9") (pintype "unspecified"))
    )
    (net (code "110") (name "unconnected-(U1-PadGND)") (class "Default")
      (node (ref "U1") (pin "GND") (pinfunction "GND_GND") (pintype "unspecified"))
    )
    (net (code "111") (name "unconnected-(U1-PadSCL)") (class "Default")
      (node (ref "U1") (pin "SCL") (pinfunction "SCL_SCL") (pintype "unspecified"))
    )
    (net (code "112") (name "unconnected-(U1-PadSDA)") (class "Default")
      (node (ref "U1") (pin "SDA") (pinfunction "SDA_SDA") (pintype "unspecified"))
    )
    (net (code "113") (name "unconnected-(U1-PadVIN)") (class "Default")
      (node (ref "U1") (pin "VIN") (pinfunction "VIN_VIN") (pintype "unspecified"))
    )
    (net (code "114") (name "unconnected-(U1-RESET-Pad88)") (class "Default")
      (node (ref "U1") (pin "88") (pinfunction "RESET_88") (pintype "unspecified"))
    )
    (net (code "115") (name "unconnected-(U1-RX0->0-Pad18)") (class "Default")
      (node (ref "U1") (pin "18") (pinfunction "RX0->0_18") (pintype "unspecified"))
    )
    (net (code "116") (name "unconnected-(U1-RX1->19-Pad24)") (class "Default")
      (node (ref "U1") (pin "24") (pinfunction "RX1->19_24") (pintype "unspecified"))
    )
    (net (code "117") (name "unconnected-(U1-RX2->17-Pad22)") (class "Default")
      (node (ref "U1") (pin "22") (pinfunction "RX2->17_22") (pintype "unspecified"))
    )
    (net (code "118") (name "unconnected-(U1-RX3->15-Pad20)") (class "Default")
      (node (ref "U1") (pin "20") (pinfunction "RX3->15_20") (pintype "unspecified"))
    )
    (net (code "119") (name "unconnected-(U1-SCK-Pad87)") (class "Default")
      (node (ref "U1") (pin "87") (pinfunction "SCK_87") (pintype "unspecified"))
    )
    (net (code "120") (name "unconnected-(U1-SDA_20-PadSDA2)") (class "Default")
      (node (ref "U1") (pin "SDA2") (pinfunction "SDA_20_SDA2") (pintype "unspecified"))
    )
    (net (code "121") (name "unconnected-(U1-SDL_21-PadSCL2)") (class "Default")
      (node (ref "U1") (pin "SCL2") (pinfunction "SDL_21_SCL2") (pintype "unspecified"))
    )
    (net (code "122") (name "unconnected-(U1-TX0->1-Pad17)") (class "Default")
      (node (ref "U1") (pin "17") (pinfunction "TX0->1_17") (pintype "unspecified"))
    )
    (net (code "123") (name "unconnected-(U1-TX1->18-Pad23)") (class "Default")
      (node (ref "U1") (pin "23") (pinfunction "TX1->18_23") (pintype "unspecified"))
    )
    (net (code "124") (name "unconnected-(U1-TX2->16-Pad21)") (class "Default")
      (node (ref "U1") (pin "21") (pinfunction "TX2->16_21") (pintype "unspecified"))
    )
    (net (code "125") (name "unconnected-(U1-TX3->14-Pad19)") (class "Default")
      (node (ref "U1") (pin "19") (pinfunction "TX3->14_19") (pintype "unspecified"))
    )
    (net (code "126") (name "unconnected-(U1-reset-Pad84)") (class "Default")
      (node (ref "U1") (pin "84") (pinfunction "reset_84") (pintype "unspecified"))
    )
    (net (code "127") (name "unconnected-(U2-CLR-Pad13)") (class "Default")
      (node (ref "U2") (pin "13") (pinfunction "CLR_13") (pintype "unspecified"))
    )
    (net (code "128") (name "unconnected-(U2-D-Pad2)") (class "Default")
      (node (ref "U2") (pin "2") (pinfunction "D_2") (pintype "unspecified"))
    )
    (net (code "129") (name "unconnected-(U2-Q-Pad5)") (class "Default")
      (node (ref "U2") (pin "5") (pinfunction "Q_5") (pintype "unspecified"))
    )
    (net (code "130") (name "unconnected-(U6-3E-Pad6)") (class "Default")
      (node (ref "U6") (pin "6") (pinfunction "3E_6") (pintype "unspecified"))
    )
    (net (code "131") (name "unconnected-(U6-3Y-Pad8)") (class "Default")
      (node (ref "U6") (pin "8") (pinfunction "3Y_8") (pintype "unspecified"))
    )
    (net (code "132") (name "unconnected-(U6-3Z-Pad9)") (class "Default")
      (node (ref "U6") (pin "9") (pinfunction "3Z_9") (pintype "unspecified"))
    )
    (net (code "133") (name "unconnected-(U7-D4-Pad13)") (class "Default")
      (node (ref "U7") (pin "13") (pinfunction "D4_13") (pintype "unspecified"))
    )
    (net (code "134") (name "unconnected-(U7-D5-Pad14)") (class "Default")
      (node (ref "U7") (pin "14") (pinfunction "D5_14") (pintype "unspecified"))
    )
    (net (code "135") (name "unconnected-(U7-D6-Pad17)") (class "Default")
      (node (ref "U7") (pin "17") (pinfunction "D6_17") (pintype "unspecified"))
    )
    (net (code "136") (name "unconnected-(U7-D7-Pad18)") (class "Default")
      (node (ref "U7") (pin "18") (pinfunction "D7_18") (pintype "unspecified"))
    )
    (net (code "137") (name "unconnected-(U7-Q4-Pad12)") (class "Default")
      (node (ref "U7") (pin "12") (pinfunction "Q4_12") (pintype "unspecified"))
    )
    (net (code "138") (name "unconnected-(U7-Q5-Pad15)") (class "Default")
      (node (ref "U7") (pin "15") (pinfunction "Q5_15") (pintype "unspecified"))
    )
    (net (code "139") (name "unconnected-(U7-Q6-Pad16)") (class "Default")
      (node (ref "U7") (pin "16") (pinfunction "Q6_16") (pintype "unspecified"))
    )
    (net (code "140") (name "unconnected-(U7-Q7-Pad19)") (class "Default")
      (node (ref "U7") (pin "19") (pinfunction "Q7_19") (pintype "unspecified"))
    )
    (net (code "141") (name "{slash}IRQ") (class "Default")
      (node (ref "U1") (pin "36") (pinfunction "29_36") (pintype "unspecified"))
      (node (ref "U7") (pin "5") (pinfunction "Q1_5") (pintype "unspecified"))
    )
    (net (code "142") (name "{slash}IRQ_BUS") (class "Default")
      (node (ref "J1") (pin "26") (pinfunction "4_26") (pintype "unspecified"))
      (node (ref "U7") (pin "4") (pinfunction "D1_4") (pintype "unspecified"))
    )
    (net (code "143") (name "{slash}NMI") (class "Default")
      (node (ref "U1") (pin "38") (pinfunction "31_38") (pintype "unspecified"))
      (node (ref "U7") (pin "2") (pinfunction "Q0_2") (pintype "unspecified"))
    )
    (net (code "144") (name "{slash}NMI_BUS") (class "Default")
      (node (ref "J1") (pin "25") (pinfunction "3_25") (pintype "unspecified"))
      (node (ref "U7") (pin "3") (pinfunction "D0_3") (pintype "unspecified"))
    )
    (net (code "145") (name "{slash}REFRESH_BUS") (class "Default")
      (node (ref "J1") (pin "23") (pinfunction "1_23") (pintype "unspecified"))
    )
    (net (code "146") (name "{slash}RESET_BUS") (class "Default")
      (node (ref "J1") (pin "24") (pinfunction "2_24") (pintype "unspecified"))
      (node (ref "KEYBOARD") (pin "1") (pinfunction "1_1") (pintype "input"))
      (node (ref "U1") (pin "73") (pinfunction "A5_73") (pintype "unspecified"))
    )
  )
)
